# amp-LNA-S-band-TQP3M9037.net
KiCad netlist of a schematic drawn in EAGLE
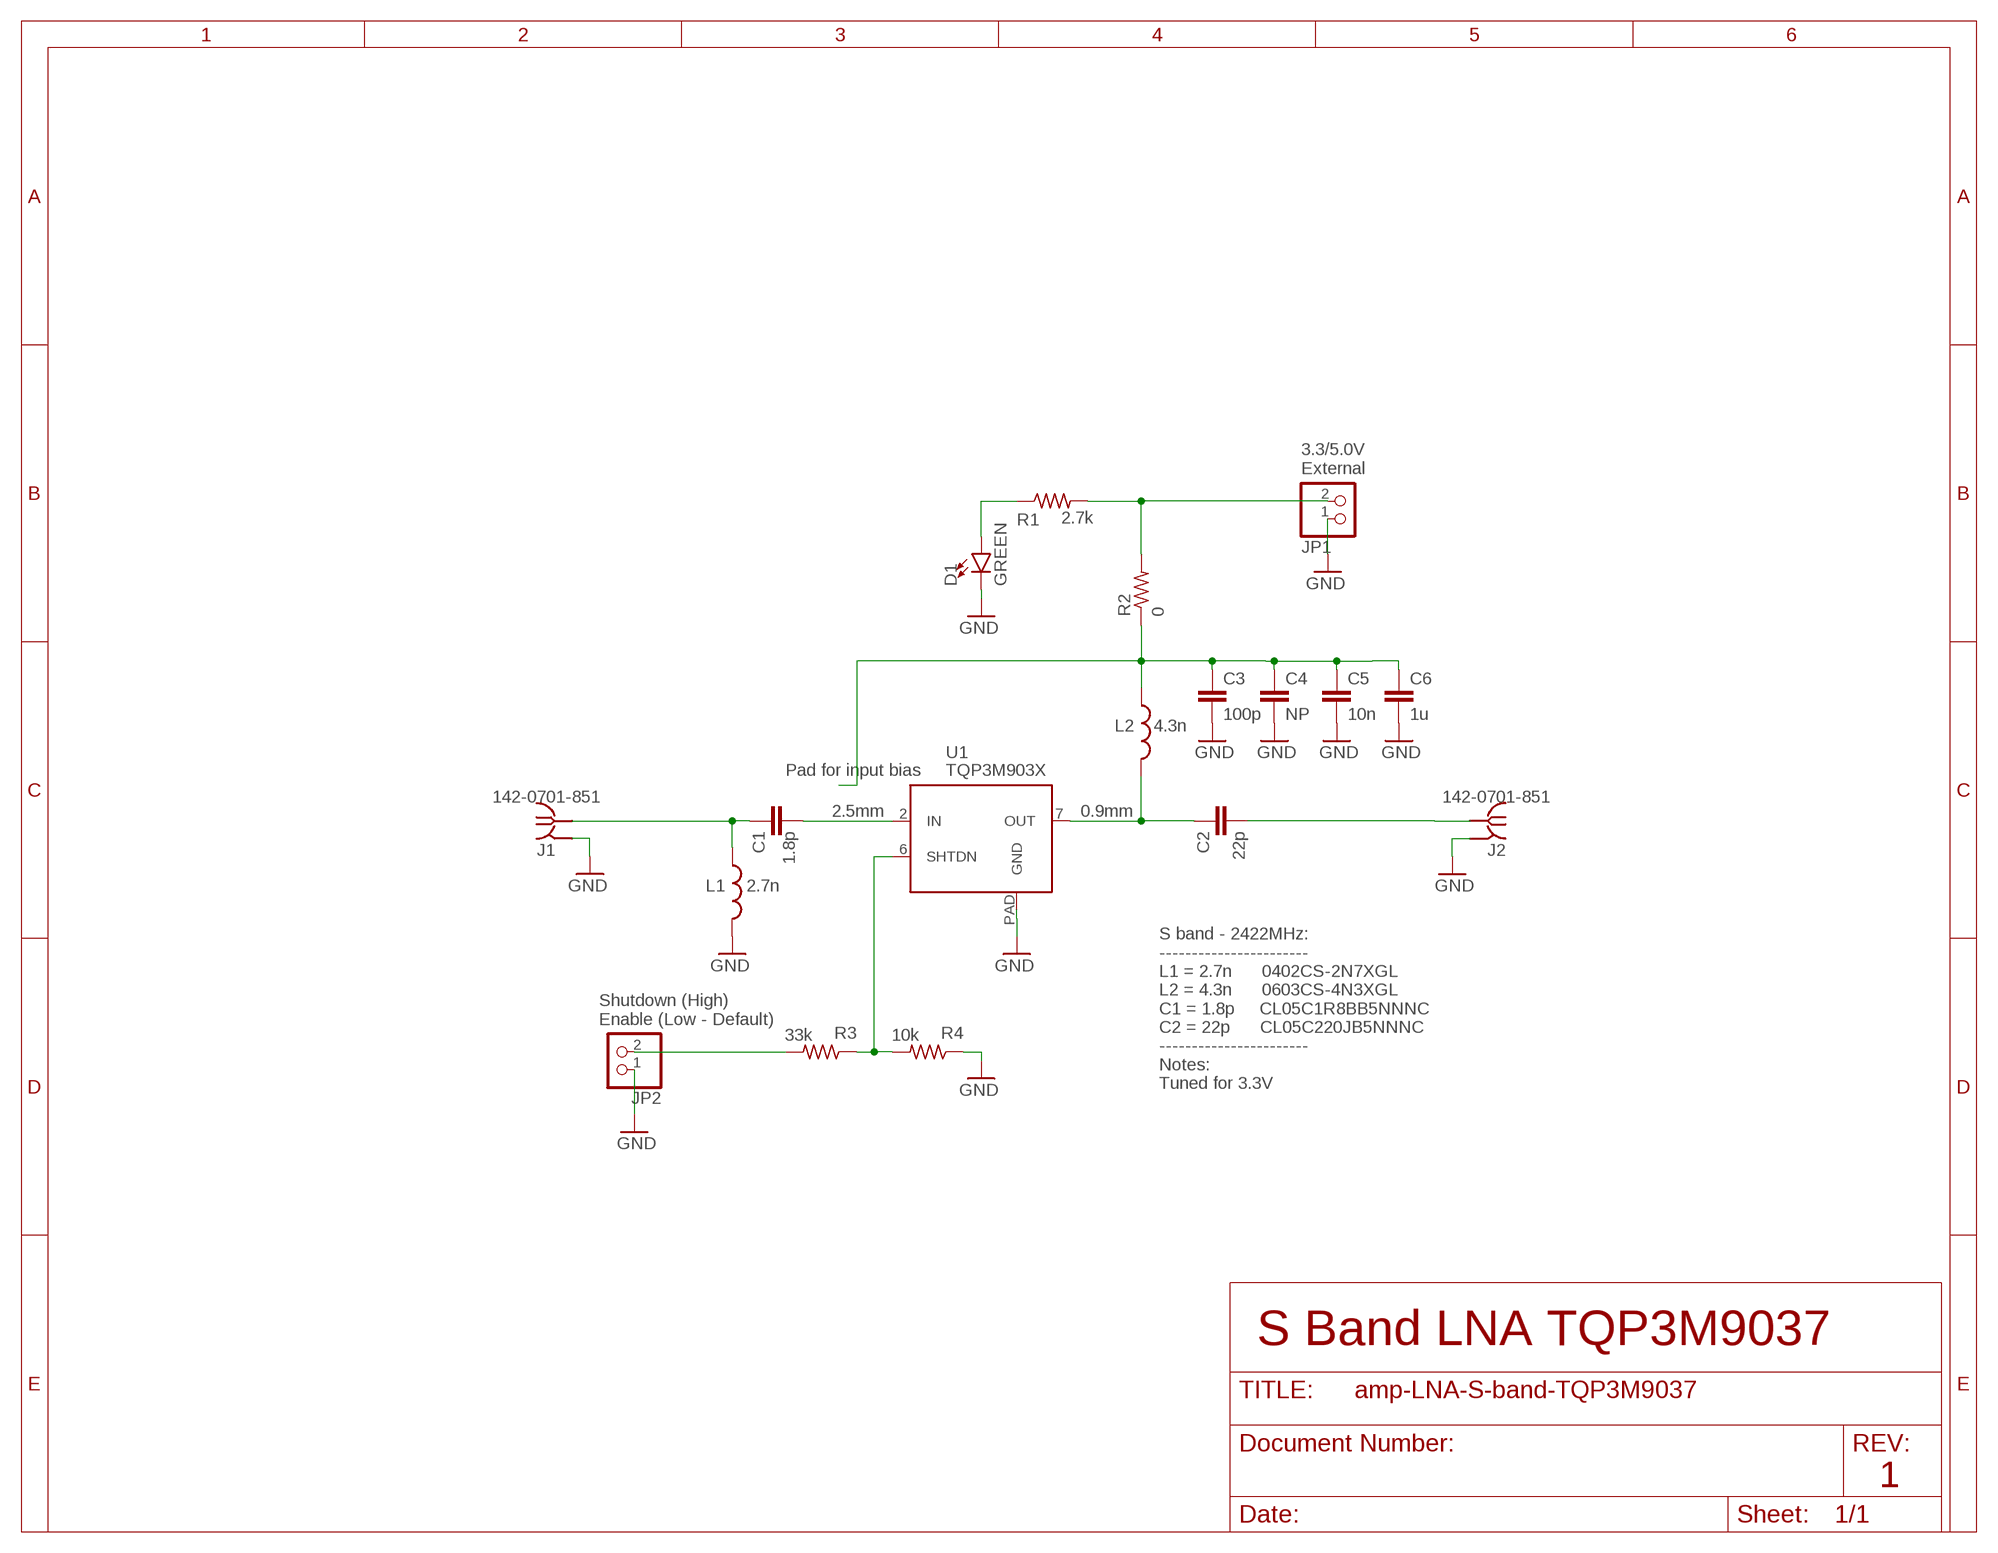
[diagram p0: schematic, sheet 1]

(export (version "E")
  (design (tool "Eeschema 10.0.6"))
  (components
    (comp (ref "C1")
      (value "1.8p")
      (footprint "eagle-import:.0402-C-NOSILK")
      (libsource (lib "eagle-import") (part "C-EU0402-C-NOSILK"))
    )
    (comp (ref "C2")
      (value "22p")
      (footprint "eagle-import:.0402-C-NOSILK")
      (libsource (lib "eagle-import") (part "C-EU0402-C-NOSILK"))
    )
    (comp (ref "C3")
      (value "100p")
      (footprint "eagle-import:.0603-B-NOSILK")
      (libsource (lib "eagle-import") (part "C-EU0603-B-NOSILK"))
    )
    (comp (ref "C4")
      (value "NP")
      (footprint "eagle-import:.0603-B-NOSILK")
      (libsource (lib "eagle-import") (part "C-EU0603-B-NOSILK"))
    )
    (comp (ref "C5")
      (value "10n")
      (footprint "eagle-import:.0603-B-NOSILK")
      (libsource (lib "eagle-import") (part "C-EU0603-B-NOSILK"))
    )
    (comp (ref "C6")
      (value "1u")
      (footprint "eagle-import:.0603-B-NOSILK")
      (libsource (lib "eagle-import") (part "C-EU0603-B-NOSILK"))
    )
    (comp (ref "D1")
      (value "GREEN")
      (footprint "eagle-import:LED-0603")
      (libsource (lib "eagle-import") (part "LED-GREEN0603"))
    )
    (comp (ref "J1")
      (value "142-0701-851")
      (footprint "eagle-import:142-0701-851")
      (libsource (lib "eagle-import") (part "142-0701-851"))
    )
    (comp (ref "J2")
      (value "142-0701-851")
      (footprint "eagle-import:142-0701-851")
      (libsource (lib "eagle-import") (part "142-0701-851"))
    )
    (comp (ref "JP1")
      (value "PINHD-1X2")
      (footprint "eagle-import:1X02")
      (libsource (lib "eagle-import") (part "PINHD-1X2"))
    )
    (comp (ref "JP2")
      (value "PINHD-1X2")
      (footprint "eagle-import:1X02")
      (libsource (lib "eagle-import") (part "PINHD-1X2"))
    )
    (comp (ref "L1")
      (value "2.7n")
      (footprint "eagle-import:.0402-C-NOSILK")
      (libsource (lib "eagle-import") (part "L-US0402-C-NOSILK"))
    )
    (comp (ref "L2")
      (value "4.3n")
      (footprint "eagle-import:.0603-C-NOSILK")
      (libsource (lib "eagle-import") (part "L-US0603-C-NOSILK"))
    )
    (comp (ref "R1")
      (value "2.7k")
      (footprint "eagle-import:.0603-B-NOSILK")
      (libsource (lib "eagle-import") (part "R-US_0603-B-NOSILK"))
    )
    (comp (ref "R2")
      (value "0")
      (footprint "eagle-import:.0603-B-NOSILK")
      (libsource (lib "eagle-import") (part "R-US_0603-B-NOSILK"))
    )
    (comp (ref "R3")
      (value "33k")
      (footprint "eagle-import:.0603-B-NOSILK")
      (libsource (lib "eagle-import") (part "R-US_0603-B-NOSILK"))
    )
    (comp (ref "R4")
      (value "10k")
      (footprint "eagle-import:.0603-B-NOSILK")
      (libsource (lib "eagle-import") (part "R-US_0603-B-NOSILK"))
    )
    (comp (ref "U1")
      (value "TQP3M903X")
      (footprint "eagle-import:DFN8-2X2-WITH-PAD")
      (libsource (lib "eagle-import") (part "TQP3M903X"))
    )
  )
  (nets
    (net (code "1") (name "GND") (class "Default")
      (node (ref "C3") (pin "2") (pinfunction "2_2") (pintype "passive"))
      (node (ref "C4") (pin "2") (pinfunction "2_2") (pintype "passive"))
      (node (ref "C5") (pin "2") (pinfunction "2_2") (pintype "passive"))
      (node (ref "C6") (pin "2") (pinfunction "2_2") (pintype "passive"))
      (node (ref "D1") (pin "C") (pinfunction "C_C") (pintype "passive"))
      (node (ref "J1") (pin "GND1") (pinfunction "GND_GND1") (pintype "bidirectional"))
      (node (ref "J1") (pin "GND2") (pinfunction "GND_GND2") (pintype "bidirectional"))
      (node (ref "J1") (pin "GND3") (pinfunction "GND_GND3") (pintype "bidirectional"))
      (node (ref "J1") (pin "GND4") (pinfunction "GND_GND4") (pintype "bidirectional"))
      (node (ref "J2") (pin "GND1") (pinfunction "GND_GND1") (pintype "bidirectional"))
      (node (ref "J2") (pin "GND2") (pinfunction "GND_GND2") (pintype "bidirectional"))
      (node (ref "J2") (pin "GND3") (pinfunction "GND_GND3") (pintype "bidirectional"))
      (node (ref "J2") (pin "GND4") (pinfunction "GND_GND4") (pintype "bidirectional"))
      (node (ref "JP1") (pin "1") (pinfunction "1_1") (pintype "passive"))
      (node (ref "JP2") (pin "1") (pinfunction "1_1") (pintype "passive"))
      (node (ref "L1") (pin "2") (pinfunction "2_2") (pintype "passive"))
      (node (ref "R4") (pin "1") (pinfunction "1_1") (pintype "passive"))
      (node (ref "U1") (pin "PAD") (pinfunction "GND_PAD") (pintype "power_in"))
    )
    (net (code "2") (name "Net-(C3-Pad1)") (class "Default")
      (node (ref "C3") (pin "1") (pinfunction "1_1") (pintype "passive"))
      (node (ref "C4") (pin "1") (pinfunction "1_1") (pintype "passive"))
      (node (ref "C5") (pin "1") (pinfunction "1_1") (pintype "passive"))
      (node (ref "C6") (pin "1") (pinfunction "1_1") (pintype "passive"))
      (node (ref "L2") (pin "1") (pinfunction "1_1") (pintype "passive"))
      (node (ref "R2") (pin "1") (pinfunction "1_1") (pintype "passive"))
    )
    (net (code "3") (name "Net-(D1-PadA)") (class "Default")
      (node (ref "D1") (pin "A") (pinfunction "A_A") (pintype "passive"))
      (node (ref "R1") (pin "1") (pinfunction "1_1") (pintype "passive"))
    )
    (net (code "4") (name "Net-(J1-RF)") (class "Default")
      (node (ref "C1") (pin "1") (pinfunction "1_1") (pintype "passive"))
      (node (ref "J1") (pin "RF1") (pinfunction "RF_RF1") (pintype "bidirectional"))
      (node (ref "L1") (pin "1") (pinfunction "1_1") (pintype "passive"))
    )
    (net (code "5") (name "Net-(J2-RF)") (class "Default")
      (node (ref "C2") (pin "2") (pinfunction "2_2") (pintype "passive"))
      (node (ref "J2") (pin "RF1") (pinfunction "RF_RF1") (pintype "bidirectional"))
    )
    (net (code "6") (name "Net-(JP1-Pad2)") (class "Default")
      (node (ref "JP1") (pin "2") (pinfunction "2_2") (pintype "passive"))
      (node (ref "R1") (pin "2") (pinfunction "2_2") (pintype "passive"))
      (node (ref "R2") (pin "2") (pinfunction "2_2") (pintype "passive"))
    )
    (net (code "7") (name "Net-(JP2-Pad2)") (class "Default")
      (node (ref "JP2") (pin "2") (pinfunction "2_2") (pintype "passive"))
      (node (ref "R3") (pin "2") (pinfunction "2_2") (pintype "passive"))
    )
    (net (code "8") (name "Net-(U1-IN)") (class "Default")
      (node (ref "C1") (pin "2") (pinfunction "2_2") (pintype "passive"))
      (node (ref "U1") (pin "2") (pinfunction "IN_2") (pintype "input"))
    )
    (net (code "9") (name "Net-(U1-OUT)") (class "Default")
      (node (ref "C2") (pin "1") (pinfunction "1_1") (pintype "passive"))
      (node (ref "L2") (pin "2") (pinfunction "2_2") (pintype "passive"))
      (node (ref "U1") (pin "7") (pinfunction "OUT_7") (pintype "output"))
    )
    (net (code "10") (name "Net-(U1-SHTDN)") (class "Default")
      (node (ref "R3") (pin "1") (pinfunction "1_1") (pintype "passive"))
      (node (ref "R4") (pin "2") (pinfunction "2_2") (pintype "passive"))
      (node (ref "U1") (pin "6") (pinfunction "SHTDN_6") (pintype "input"))
    )
  )
)
